# mainboard.net
KiCad netlist of a schematic drawn in EAGLE
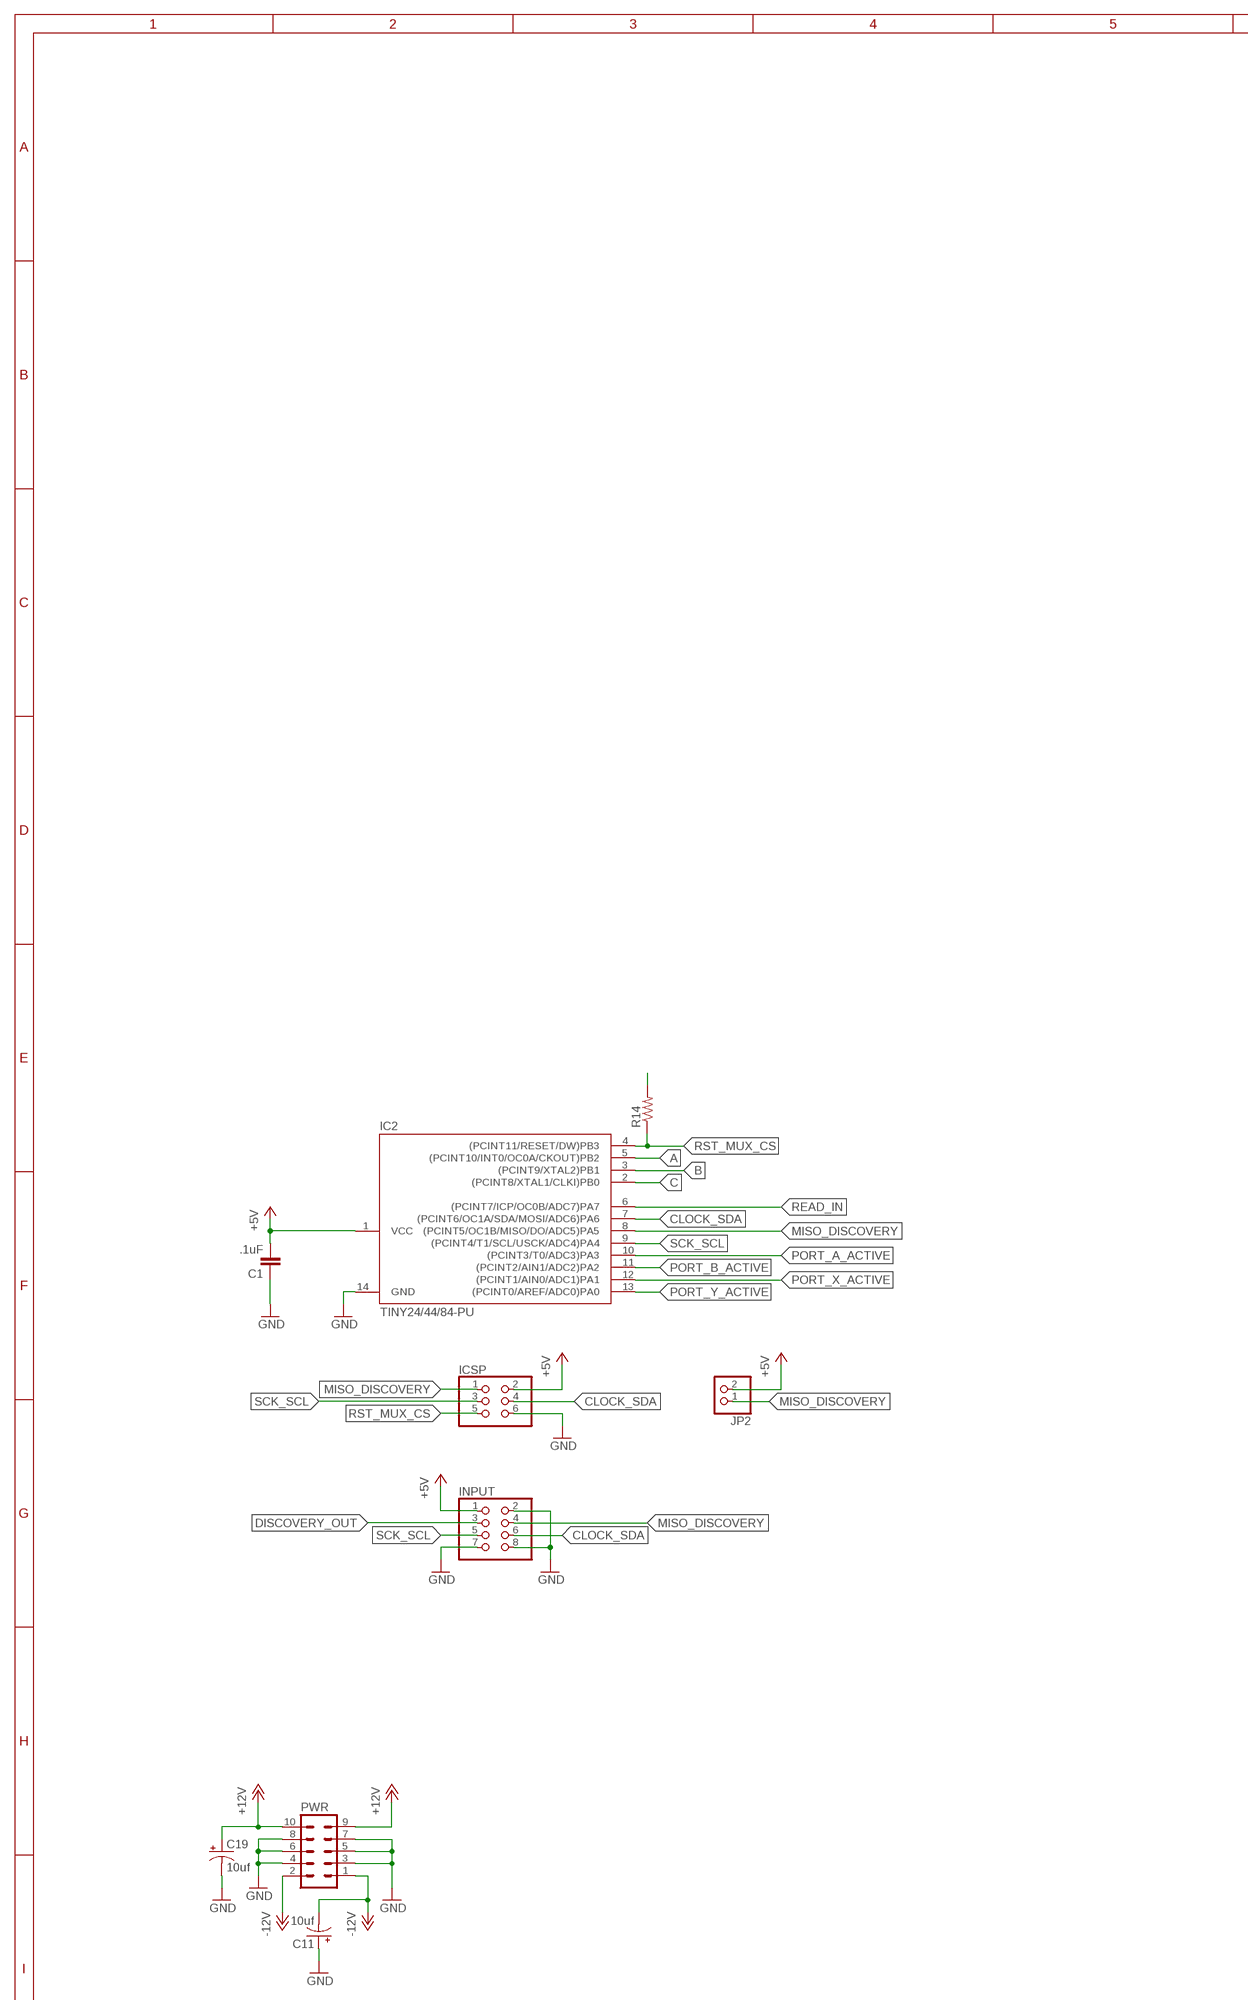
[diagram p0: schematic, sheet 1, part 1 of 2]
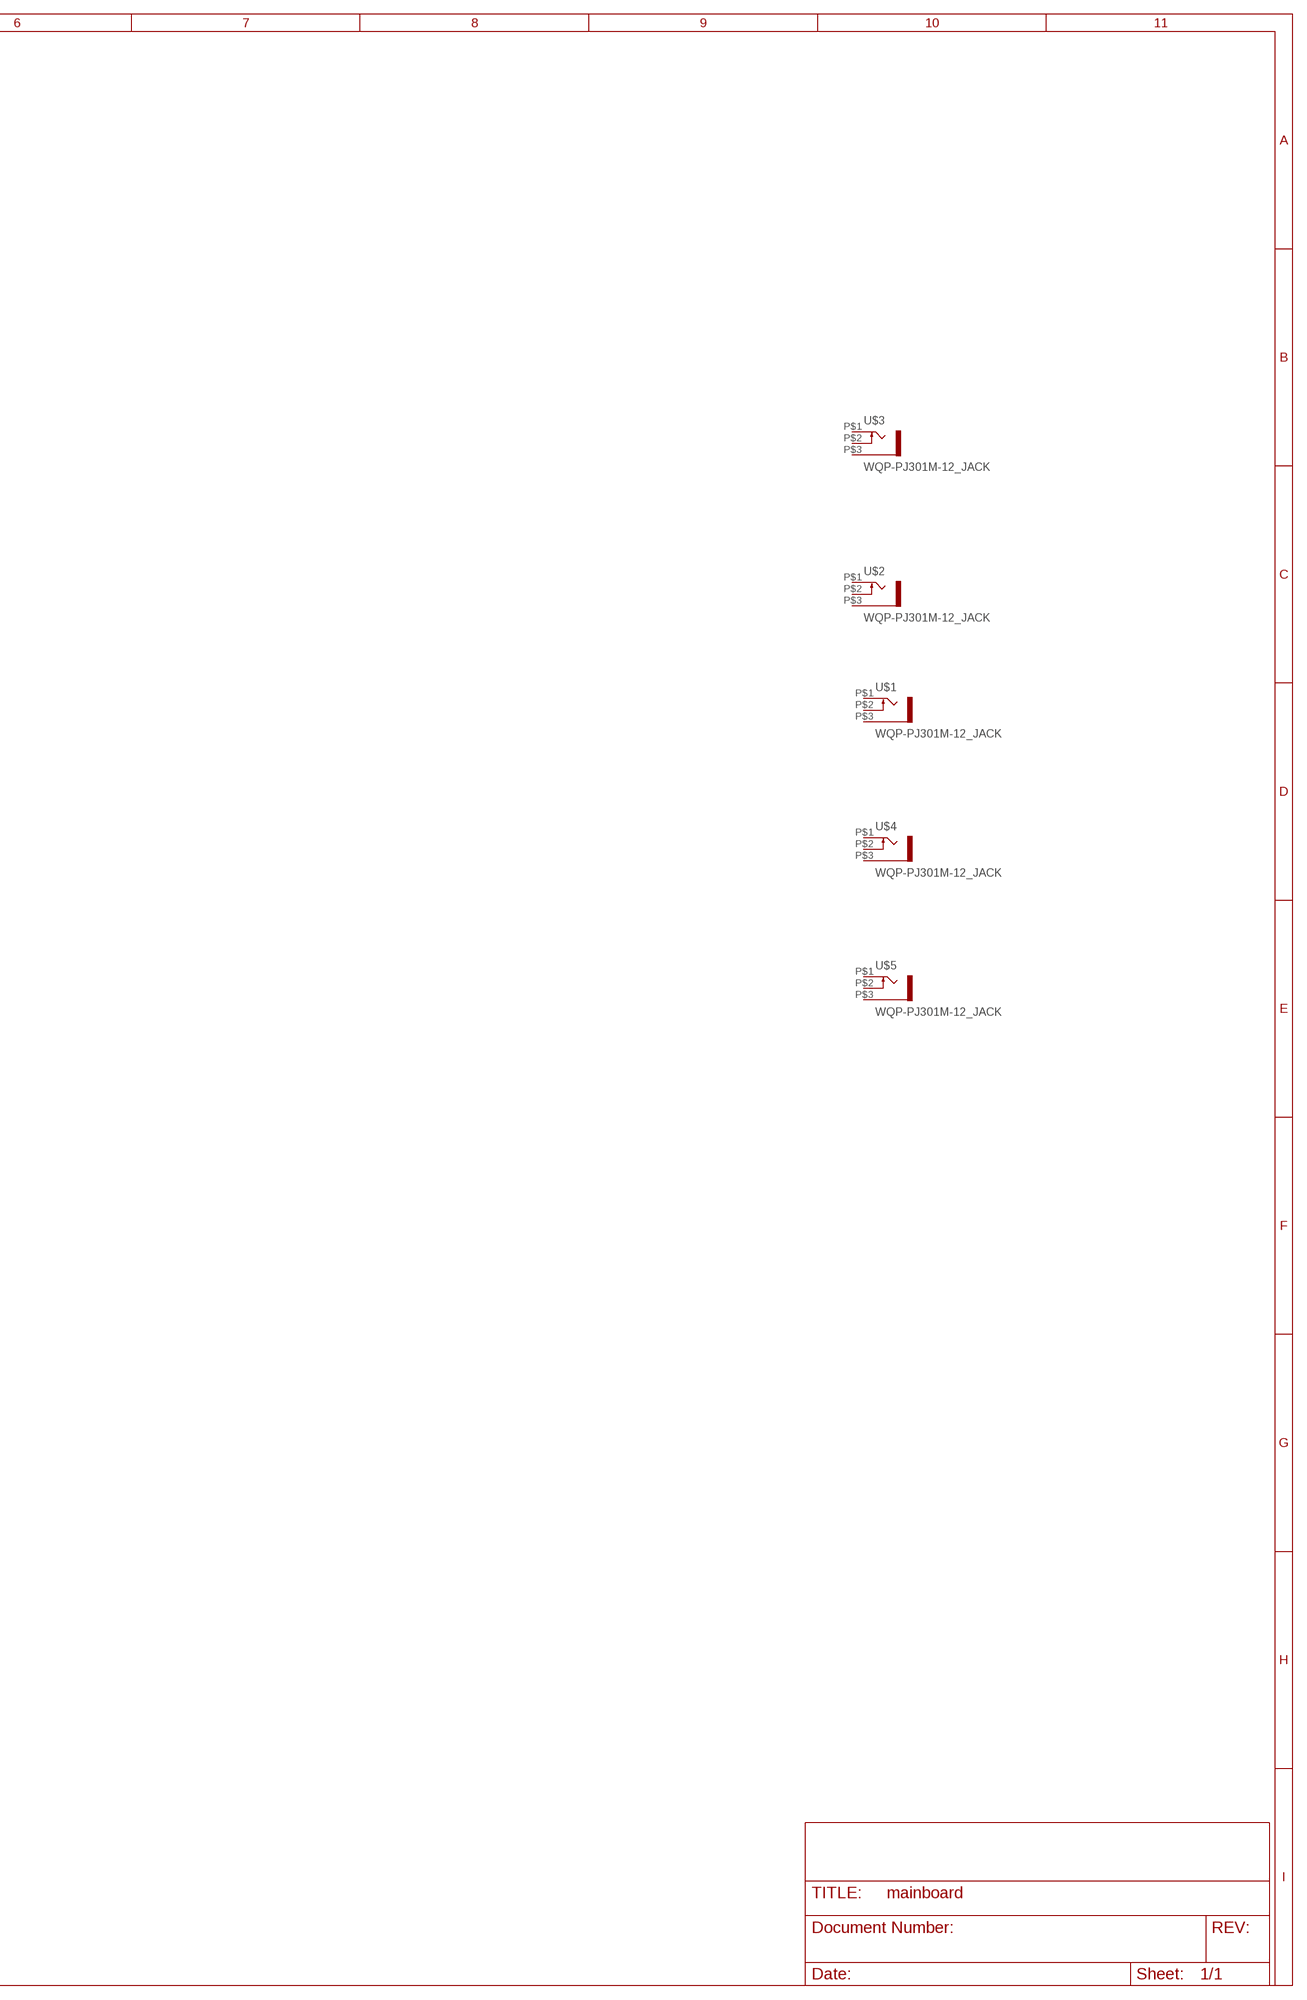
[diagram p1: schematic, sheet 1, part 2 of 2]

(export (version "E")
  (design (tool "Eeschema 10.0.6"))
  (components
    (comp (ref "C1")
      (value ".1uF")
      (footprint "eagle-import:C050-024X044")
      (libsource (lib "eagle-import") (part "C-EU050-024X044"))
    )
    (comp (ref "C11")
      (value "10uf")
      (footprint "eagle-import:E2,5-5")
      (libsource (lib "eagle-import") (part "CPOL-USE2.5-5"))
    )
    (comp (ref "C19")
      (value "10uf")
      (footprint "eagle-import:E2,5-5")
      (libsource (lib "eagle-import") (part "CPOL-USE2.5-5"))
    )
    (comp (ref "IC2")
      (value "TINY24/44/84-PU")
      (footprint "eagle-import:DIL14")
      (libsource (lib "eagle-import") (part "TINY24/44/84-PU"))
    )
    (comp (ref "ICSP")
      (value "PINHD-2X3")
      (footprint "eagle-import:2X03")
      (libsource (lib "eagle-import") (part "PINHD-2X3"))
    )
    (comp (ref "INPUT")
      (value "PINHD-2X4")
      (footprint "eagle-import:2X04")
      (libsource (lib "eagle-import") (part "PINHD-2X4"))
    )
    (comp (ref "JP2")
      (value "PINHD-1X2")
      (footprint "eagle-import:1X02")
      (libsource (lib "eagle-import") (part "PINHD-1X2"))
    )
    (comp (ref "PWR")
      (value "ML10")
      (footprint "eagle-import:ML10")
      (libsource (lib "eagle-import") (part "ML10"))
    )
    (comp (ref "R14")
      (value "R-US_0204/7")
      (footprint "eagle-import:0204_7")
      (libsource (lib "eagle-import") (part "R-US_0204/7"))
    )
    (comp (ref "U$1")
      (value "WQP-PJ301M-12_JACK")
      (footprint "eagle-import:WQP-PJ301M-12_JACK")
      (libsource (lib "eagle-import") (part "WQP-PJ301M-12_JACK"))
    )
    (comp (ref "U$2")
      (value "WQP-PJ301M-12_JACK")
      (footprint "eagle-import:WQP-PJ301M-12_JACK")
      (libsource (lib "eagle-import") (part "WQP-PJ301M-12_JACK"))
    )
    (comp (ref "U$3")
      (value "WQP-PJ301M-12_JACK")
      (footprint "eagle-import:WQP-PJ301M-12_JACK")
      (libsource (lib "eagle-import") (part "WQP-PJ301M-12_JACK"))
    )
    (comp (ref "U$4")
      (value "WQP-PJ301M-12_JACK")
      (footprint "eagle-import:WQP-PJ301M-12_JACK")
      (libsource (lib "eagle-import") (part "WQP-PJ301M-12_JACK"))
    )
    (comp (ref "U$5")
      (value "WQP-PJ301M-12_JACK")
      (footprint "eagle-import:WQP-PJ301M-12_JACK")
      (libsource (lib "eagle-import") (part "WQP-PJ301M-12_JACK"))
    )
  )
  (nets
    (net (code "1") (name "+5V") (class "Default")
      (node (ref "C1") (pin "2") (pinfunction "2_2") (pintype "passive"))
      (node (ref "IC2") (pin "1") (pinfunction "VCC_1") (pintype "power_in"))
      (node (ref "ICSP") (pin "2") (pinfunction "2_2") (pintype "passive"))
      (node (ref "INPUT") (pin "1") (pinfunction "1_1") (pintype "passive"))
      (node (ref "JP2") (pin "2") (pinfunction "2_2") (pintype "passive"))
      (node (ref "R14") (pin "2") (pinfunction "2_2") (pintype "passive"))
    )
    (net (code "2") (name "+12V") (class "Default")
      (node (ref "C19") (pin "+") (pinfunction "+_+") (pintype "passive"))
      (node (ref "PWR") (pin "10") (pinfunction "10_10") (pintype "passive"))
      (node (ref "PWR") (pin "9") (pinfunction "9_9") (pintype "passive"))
    )
    (net (code "3") (name "-12V") (class "Default")
      (node (ref "C11") (pin "-") (pinfunction "-_-") (pintype "passive"))
      (node (ref "PWR") (pin "1") (pinfunction "1_1") (pintype "passive"))
      (node (ref "PWR") (pin "2") (pinfunction "2_2") (pintype "passive"))
    )
    (net (code "4") (name "A") (class "Default")
      (node (ref "IC2") (pin "5") (pinfunction "(PCINT10/INT0/OC0A/CKOUT)PB2_5") (pintype "bidirectional"))
    )
    (net (code "5") (name "B") (class "Default")
      (node (ref "IC2") (pin "3") (pinfunction "(PCINT9/XTAL2)PB1_3") (pintype "bidirectional"))
    )
    (net (code "6") (name "C") (class "Default")
      (node (ref "IC2") (pin "2") (pinfunction "(PCINT8/XTAL1/CLKI)PB0_2") (pintype "bidirectional"))
    )
    (net (code "7") (name "CLOCK_SDA") (class "Default")
      (node (ref "IC2") (pin "7") (pinfunction "(PCINT6/OC1A/SDA/MOSI/ADC6)PA6_7") (pintype "bidirectional"))
      (node (ref "ICSP") (pin "4") (pinfunction "4_4") (pintype "passive"))
      (node (ref "INPUT") (pin "6") (pinfunction "6_6") (pintype "passive"))
    )
    (net (code "8") (name "DISCOVERY_OUT") (class "Default")
      (node (ref "INPUT") (pin "3") (pinfunction "3_3") (pintype "passive"))
    )
    (net (code "9") (name "GND") (class "Default")
      (node (ref "C1") (pin "1") (pinfunction "1_1") (pintype "passive"))
      (node (ref "C11") (pin "+") (pinfunction "+_+") (pintype "passive"))
      (node (ref "C19") (pin "-") (pinfunction "-_-") (pintype "passive"))
      (node (ref "IC2") (pin "14") (pinfunction "GND_14") (pintype "power_in"))
      (node (ref "ICSP") (pin "6") (pinfunction "6_6") (pintype "passive"))
      (node (ref "INPUT") (pin "2") (pinfunction "2_2") (pintype "passive"))
      (node (ref "INPUT") (pin "7") (pinfunction "7_7") (pintype "passive"))
      (node (ref "INPUT") (pin "8") (pinfunction "8_8") (pintype "passive"))
      (node (ref "PWR") (pin "3") (pinfunction "3_3") (pintype "passive"))
      (node (ref "PWR") (pin "4") (pinfunction "4_4") (pintype "passive"))
      (node (ref "PWR") (pin "5") (pinfunction "5_5") (pintype "passive"))
      (node (ref "PWR") (pin "6") (pinfunction "6_6") (pintype "passive"))
      (node (ref "PWR") (pin "7") (pinfunction "7_7") (pintype "passive"))
      (node (ref "PWR") (pin "8") (pinfunction "8_8") (pintype "passive"))
    )
    (net (code "10") (name "MISO_DISCOVERY") (class "Default")
      (node (ref "IC2") (pin "8") (pinfunction "(PCINT5/OC1B/MISO/DO/ADC5)PA5_8") (pintype "bidirectional"))
      (node (ref "ICSP") (pin "1") (pinfunction "1_1") (pintype "passive"))
      (node (ref "INPUT") (pin "4") (pinfunction "4_4") (pintype "passive"))
      (node (ref "JP2") (pin "1") (pinfunction "1_1") (pintype "passive"))
    )
    (net (code "11") (name "PORT_A_ACTIVE") (class "Default")
      (node (ref "IC2") (pin "10") (pinfunction "(PCINT3/T0/ADC3)PA3_10") (pintype "bidirectional"))
    )
    (net (code "12") (name "PORT_B_ACTIVE") (class "Default")
      (node (ref "IC2") (pin "11") (pinfunction "(PCINT2/AIN1/ADC2)PA2_11") (pintype "bidirectional"))
    )
    (net (code "13") (name "PORT_X_ACTIVE") (class "Default")
      (node (ref "IC2") (pin "12") (pinfunction "(PCINT1/AIN0/ADC1)PA1_12") (pintype "bidirectional"))
    )
    (net (code "14") (name "PORT_Y_ACTIVE") (class "Default")
      (node (ref "IC2") (pin "13") (pinfunction "(PCINT0/AREF/ADC0)PA0_13") (pintype "bidirectional"))
    )
    (net (code "15") (name "READ_IN") (class "Default")
      (node (ref "IC2") (pin "6") (pinfunction "(PCINT7/ICP/OC0B/ADC7)PA7_6") (pintype "bidirectional"))
    )
    (net (code "16") (name "RST_MUX_CS") (class "Default")
      (node (ref "IC2") (pin "4") (pinfunction "(PCINT11/RESET/DW)PB3_4") (pintype "bidirectional"))
      (node (ref "ICSP") (pin "5") (pinfunction "5_5") (pintype "passive"))
      (node (ref "R14") (pin "1") (pinfunction "1_1") (pintype "passive"))
    )
    (net (code "17") (name "SCK_SCL") (class "Default")
      (node (ref "IC2") (pin "9") (pinfunction "(PCINT4/T1/SCL/USCK/ADC4)PA4_9") (pintype "bidirectional"))
      (node (ref "ICSP") (pin "3") (pinfunction "3_3") (pintype "passive"))
      (node (ref "INPUT") (pin "5") (pinfunction "5_5") (pintype "passive"))
    )
    (net (code "18") (name "unconnected-(U$1-1-PadP$3)") (class "Default")
      (node (ref "U$1") (pin "P$3") (pinfunction "1_P$3") (pintype "passive"))
    )
    (net (code "19") (name "unconnected-(U$1-2-PadP$1)") (class "Default")
      (node (ref "U$1") (pin "P$1") (pinfunction "2_P$1") (pintype "passive"))
    )
    (net (code "20") (name "unconnected-(U$1-3-PadP$2)") (class "Default")
      (node (ref "U$1") (pin "P$2") (pinfunction "3_P$2") (pintype "passive"))
    )
    (net (code "21") (name "unconnected-(U$2-1-PadP$3)") (class "Default")
      (node (ref "U$2") (pin "P$3") (pinfunction "1_P$3") (pintype "passive"))
    )
    (net (code "22") (name "unconnected-(U$2-2-PadP$1)") (class "Default")
      (node (ref "U$2") (pin "P$1") (pinfunction "2_P$1") (pintype "passive"))
    )
    (net (code "23") (name "unconnected-(U$2-3-PadP$2)") (class "Default")
      (node (ref "U$2") (pin "P$2") (pinfunction "3_P$2") (pintype "passive"))
    )
    (net (code "24") (name "unconnected-(U$3-1-PadP$3)") (class "Default")
      (node (ref "U$3") (pin "P$3") (pinfunction "1_P$3") (pintype "passive"))
    )
    (net (code "25") (name "unconnected-(U$3-2-PadP$1)") (class "Default")
      (node (ref "U$3") (pin "P$1") (pinfunction "2_P$1") (pintype "passive"))
    )
    (net (code "26") (name "unconnected-(U$3-3-PadP$2)") (class "Default")
      (node (ref "U$3") (pin "P$2") (pinfunction "3_P$2") (pintype "passive"))
    )
    (net (code "27") (name "unconnected-(U$4-1-PadP$3)") (class "Default")
      (node (ref "U$4") (pin "P$3") (pinfunction "1_P$3") (pintype "passive"))
    )
    (net (code "28") (name "unconnected-(U$4-2-PadP$1)") (class "Default")
      (node (ref "U$4") (pin "P$1") (pinfunction "2_P$1") (pintype "passive"))
    )
    (net (code "29") (name "unconnected-(U$4-3-PadP$2)") (class "Default")
      (node (ref "U$4") (pin "P$2") (pinfunction "3_P$2") (pintype "passive"))
    )
    (net (code "30") (name "unconnected-(U$5-1-PadP$3)") (class "Default")
      (node (ref "U$5") (pin "P$3") (pinfunction "1_P$3") (pintype "passive"))
    )
    (net (code "31") (name "unconnected-(U$5-2-PadP$1)") (class "Default")
      (node (ref "U$5") (pin "P$1") (pinfunction "2_P$1") (pintype "passive"))
    )
    (net (code "32") (name "unconnected-(U$5-3-PadP$2)") (class "Default")
      (node (ref "U$5") (pin "P$2") (pinfunction "3_P$2") (pintype "passive"))
    )
  )
)
